# relays_1-4_DS4E.net
KiCad netlist of a schematic drawn in Altium Designer
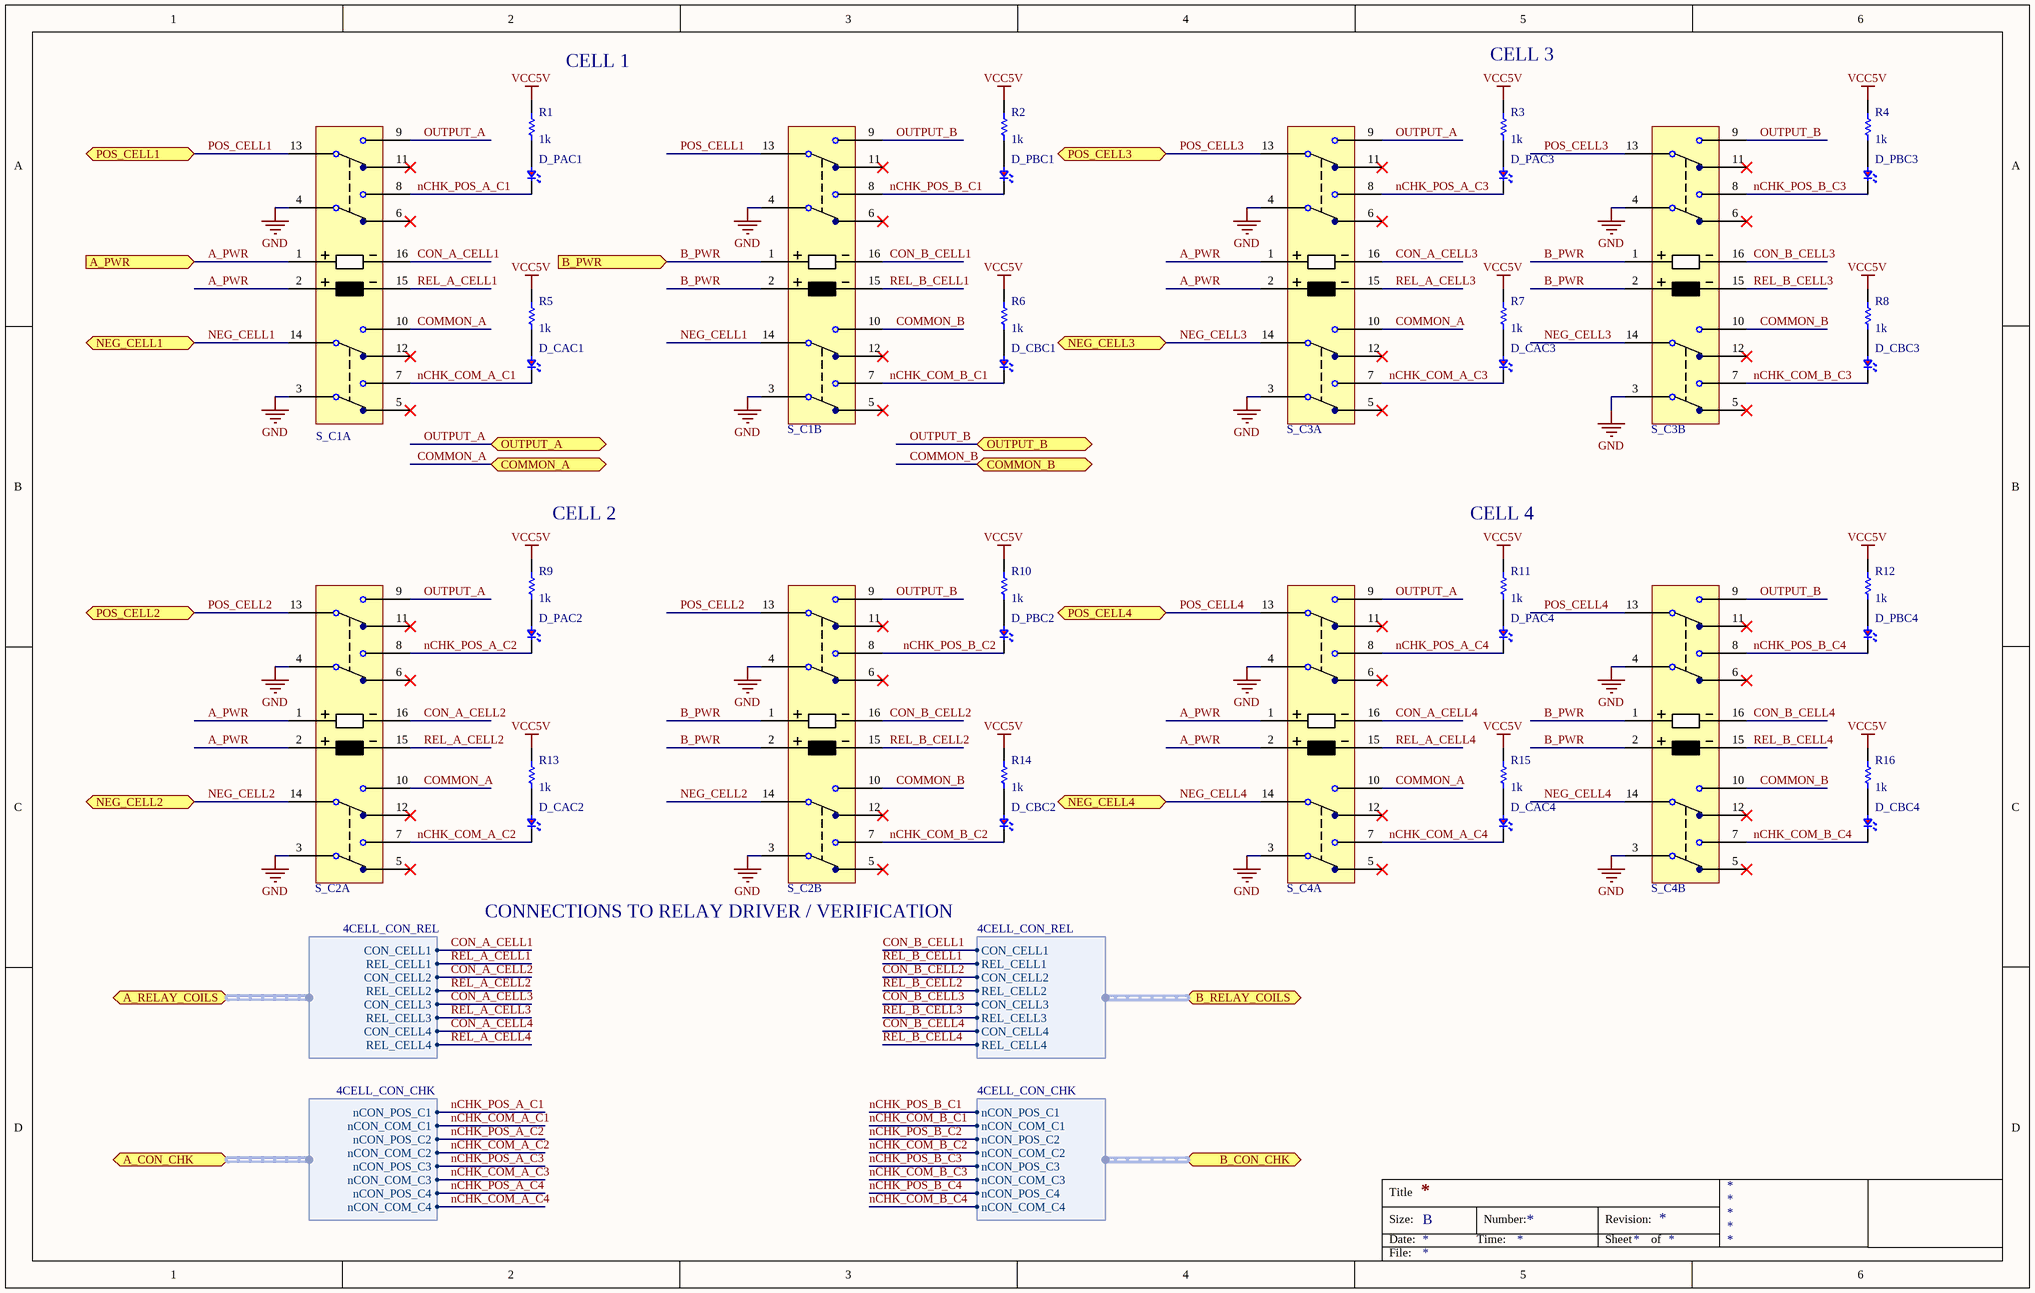
[diagram p0: relays_1-4_DS4E.SchDoc]

(export (version "E")
  (design (tool "Eeschema 10.0.6"))
  (components
    (comp (ref "D_CAC1")
      (value "Red LED")
      (footprint "LEDRD100W25D118H196")
      (description "LED 5MM RED DIFF 6\"LDS PANEL MT")
      (fields
        (field (name "MANUFACTURER") "Lumex Opto/Components Inc.")
        (field (name "MANUFACTURER PART NUMBER") "SSI-LXH600ID-150")
      )
      (libsource (lib "mechanart_oshw") (part "LED-RED"))
    )
    (comp (ref "D_CAC2")
      (value "Red LED")
      (footprint "LEDRD100W25D118H196")
      (description "LED 5MM RED DIFF 6\"LDS PANEL MT")
      (fields
        (field (name "MANUFACTURER") "Lumex Opto/Components Inc.")
        (field (name "MANUFACTURER PART NUMBER") "SSI-LXH600ID-150")
      )
      (libsource (lib "mechanart_oshw") (part "LED-RED"))
    )
    (comp (ref "D_CAC3")
      (value "Red LED")
      (footprint "LEDRD100W25D118H196")
      (description "LED 5MM RED DIFF 6\"LDS PANEL MT")
      (fields
        (field (name "MANUFACTURER") "Lumex Opto/Components Inc.")
        (field (name "MANUFACTURER PART NUMBER") "SSI-LXH600ID-150")
      )
      (libsource (lib "mechanart_oshw") (part "LED-RED"))
    )
    (comp (ref "D_CAC4")
      (value "Red LED")
      (footprint "LEDRD100W25D118H196")
      (description "LED 5MM RED DIFF 6\"LDS PANEL MT")
      (fields
        (field (name "MANUFACTURER") "Lumex Opto/Components Inc.")
        (field (name "MANUFACTURER PART NUMBER") "SSI-LXH600ID-150")
      )
      (libsource (lib "mechanart_oshw") (part "LED-RED"))
    )
    (comp (ref "D_CBC1")
      (value "Red LED")
      (footprint "LEDRD100W25D118H196")
      (description "LED 5MM RED DIFF 6\"LDS PANEL MT")
      (fields
        (field (name "MANUFACTURER") "Lumex Opto/Components Inc.")
        (field (name "MANUFACTURER PART NUMBER") "SSI-LXH600ID-150")
      )
      (libsource (lib "mechanart_oshw") (part "LED-RED"))
    )
    (comp (ref "D_CBC2")
      (value "Red LED")
      (footprint "LEDRD100W25D118H196")
      (description "LED 5MM RED DIFF 6\"LDS PANEL MT")
      (fields
        (field (name "MANUFACTURER") "Lumex Opto/Components Inc.")
        (field (name "MANUFACTURER PART NUMBER") "SSI-LXH600ID-150")
      )
      (libsource (lib "mechanart_oshw") (part "LED-RED"))
    )
    (comp (ref "D_CBC3")
      (value "Red LED")
      (footprint "LEDRD100W25D118H196")
      (description "LED 5MM RED DIFF 6\"LDS PANEL MT")
      (fields
        (field (name "MANUFACTURER") "Lumex Opto/Components Inc.")
        (field (name "MANUFACTURER PART NUMBER") "SSI-LXH600ID-150")
      )
      (libsource (lib "mechanart_oshw") (part "LED-RED"))
    )
    (comp (ref "D_CBC4")
      (value "Red LED")
      (footprint "LEDRD100W25D118H196")
      (description "LED 5MM RED DIFF 6\"LDS PANEL MT")
      (fields
        (field (name "MANUFACTURER") "Lumex Opto/Components Inc.")
        (field (name "MANUFACTURER PART NUMBER") "SSI-LXH600ID-150")
      )
      (libsource (lib "mechanart_oshw") (part "LED-RED"))
    )
    (comp (ref "D_PAC1")
      (value "Red LED")
      (footprint "LEDRD100W25D118H196")
      (description "LED 5MM RED DIFF 6\"LDS PANEL MT")
      (fields
        (field (name "MANUFACTURER") "Lumex Opto/Components Inc.")
        (field (name "MANUFACTURER PART NUMBER") "SSI-LXH600ID-150")
      )
      (libsource (lib "mechanart_oshw") (part "LED-RED"))
    )
    (comp (ref "D_PAC2")
      (value "Red LED")
      (footprint "LEDRD100W25D118H196")
      (description "LED 5MM RED DIFF 6\"LDS PANEL MT")
      (fields
        (field (name "MANUFACTURER") "Lumex Opto/Components Inc.")
        (field (name "MANUFACTURER PART NUMBER") "SSI-LXH600ID-150")
      )
      (libsource (lib "mechanart_oshw") (part "LED-RED"))
    )
    (comp (ref "D_PAC3")
      (value "Red LED")
      (footprint "LEDRD100W25D118H196")
      (description "LED 5MM RED DIFF 6\"LDS PANEL MT")
      (fields
        (field (name "MANUFACTURER") "Lumex Opto/Components Inc.")
        (field (name "MANUFACTURER PART NUMBER") "SSI-LXH600ID-150")
      )
      (libsource (lib "mechanart_oshw") (part "LED-RED"))
    )
    (comp (ref "D_PAC4")
      (value "Red LED")
      (footprint "LEDRD100W25D118H196")
      (description "LED 5MM RED DIFF 6\"LDS PANEL MT")
      (fields
        (field (name "MANUFACTURER") "Lumex Opto/Components Inc.")
        (field (name "MANUFACTURER PART NUMBER") "SSI-LXH600ID-150")
      )
      (libsource (lib "mechanart_oshw") (part "LED-RED"))
    )
    (comp (ref "D_PBC1")
      (value "Red LED")
      (footprint "LEDRD100W25D118H196")
      (description "LED 5MM RED DIFF 6\"LDS PANEL MT")
      (fields
        (field (name "MANUFACTURER") "Lumex Opto/Components Inc.")
        (field (name "MANUFACTURER PART NUMBER") "SSI-LXH600ID-150")
      )
      (libsource (lib "mechanart_oshw") (part "LED-RED"))
    )
    (comp (ref "D_PBC2")
      (value "Red LED")
      (footprint "LEDRD100W25D118H196")
      (description "LED 5MM RED DIFF 6\"LDS PANEL MT")
      (fields
        (field (name "MANUFACTURER") "Lumex Opto/Components Inc.")
        (field (name "MANUFACTURER PART NUMBER") "SSI-LXH600ID-150")
      )
      (libsource (lib "mechanart_oshw") (part "LED-RED"))
    )
    (comp (ref "D_PBC3")
      (value "Red LED")
      (footprint "LEDRD100W25D118H196")
      (description "LED 5MM RED DIFF 6\"LDS PANEL MT")
      (fields
        (field (name "MANUFACTURER") "Lumex Opto/Components Inc.")
        (field (name "MANUFACTURER PART NUMBER") "SSI-LXH600ID-150")
      )
      (libsource (lib "mechanart_oshw") (part "LED-RED"))
    )
    (comp (ref "D_PBC4")
      (value "Red LED")
      (footprint "LEDRD100W25D118H196")
      (description "LED 5MM RED DIFF 6\"LDS PANEL MT")
      (fields
        (field (name "MANUFACTURER") "Lumex Opto/Components Inc.")
        (field (name "MANUFACTURER PART NUMBER") "SSI-LXH600ID-150")
      )
      (libsource (lib "mechanart_oshw") (part "LED-RED"))
    )
    (comp (ref "R1")
      (value "1k")
      (footprint "RESC2012X75L55N")
      (description "RES SMD 1K OHM 5% 1/2W 0805")
      (fields
        (field (name "MANUFACTURER") "Panasonic Electronic Components")
        (field (name "MANUFACTURER PART NUMBER") "ERJ-P06J102V")
      )
      (libsource (lib "mechanart_oshw") (part "ResSMT"))
    )
    (comp (ref "R2")
      (value "1k")
      (footprint "RESC2012X75L55N")
      (description "RES SMD 1K OHM 5% 1/2W 0805")
      (fields
        (field (name "MANUFACTURER") "Panasonic Electronic Components")
        (field (name "MANUFACTURER PART NUMBER") "ERJ-P06J102V")
      )
      (libsource (lib "mechanart_oshw") (part "ResSMT"))
    )
    (comp (ref "R3")
      (value "1k")
      (footprint "RESC2012X75L55N")
      (description "RES SMD 1K OHM 5% 1/2W 0805")
      (fields
        (field (name "MANUFACTURER") "Panasonic Electronic Components")
        (field (name "MANUFACTURER PART NUMBER") "ERJ-P06J102V")
      )
      (libsource (lib "mechanart_oshw") (part "ResSMT"))
    )
    (comp (ref "R4")
      (value "1k")
      (footprint "RESC2012X75L55N")
      (description "RES SMD 1K OHM 5% 1/2W 0805")
      (fields
        (field (name "MANUFACTURER") "Panasonic Electronic Components")
        (field (name "MANUFACTURER PART NUMBER") "ERJ-P06J102V")
      )
      (libsource (lib "mechanart_oshw") (part "ResSMT"))
    )
    (comp (ref "R5")
      (value "1k")
      (footprint "RESC2012X75L55N")
      (description "RES SMD 1K OHM 5% 1/2W 0805")
      (fields
        (field (name "MANUFACTURER") "Panasonic Electronic Components")
        (field (name "MANUFACTURER PART NUMBER") "ERJ-P06J102V")
      )
      (libsource (lib "mechanart_oshw") (part "ResSMT"))
    )
    (comp (ref "R6")
      (value "1k")
      (footprint "RESC2012X75L55N")
      (description "RES SMD 1K OHM 5% 1/2W 0805")
      (fields
        (field (name "MANUFACTURER") "Panasonic Electronic Components")
        (field (name "MANUFACTURER PART NUMBER") "ERJ-P06J102V")
      )
      (libsource (lib "mechanart_oshw") (part "ResSMT"))
    )
    (comp (ref "R7")
      (value "1k")
      (footprint "RESC2012X75L55N")
      (description "RES SMD 1K OHM 5% 1/2W 0805")
      (fields
        (field (name "MANUFACTURER") "Panasonic Electronic Components")
        (field (name "MANUFACTURER PART NUMBER") "ERJ-P06J102V")
      )
      (libsource (lib "mechanart_oshw") (part "ResSMT"))
    )
    (comp (ref "R8")
      (value "1k")
      (footprint "RESC2012X75L55N")
      (description "RES SMD 1K OHM 5% 1/2W 0805")
      (fields
        (field (name "MANUFACTURER") "Panasonic Electronic Components")
        (field (name "MANUFACTURER PART NUMBER") "ERJ-P06J102V")
      )
      (libsource (lib "mechanart_oshw") (part "ResSMT"))
    )
    (comp (ref "R9")
      (value "1k")
      (footprint "RESC2012X75L55N")
      (description "RES SMD 1K OHM 5% 1/2W 0805")
      (fields
        (field (name "MANUFACTURER") "Panasonic Electronic Components")
        (field (name "MANUFACTURER PART NUMBER") "ERJ-P06J102V")
      )
      (libsource (lib "mechanart_oshw") (part "ResSMT"))
    )
    (comp (ref "R10")
      (value "1k")
      (footprint "RESC2012X75L55N")
      (description "RES SMD 1K OHM 5% 1/2W 0805")
      (fields
        (field (name "MANUFACTURER") "Panasonic Electronic Components")
        (field (name "MANUFACTURER PART NUMBER") "ERJ-P06J102V")
      )
      (libsource (lib "mechanart_oshw") (part "ResSMT"))
    )
    (comp (ref "R11")
      (value "1k")
      (footprint "RESC2012X75L55N")
      (description "RES SMD 1K OHM 5% 1/2W 0805")
      (fields
        (field (name "MANUFACTURER") "Panasonic Electronic Components")
        (field (name "MANUFACTURER PART NUMBER") "ERJ-P06J102V")
      )
      (libsource (lib "mechanart_oshw") (part "ResSMT"))
    )
    (comp (ref "R12")
      (value "1k")
      (footprint "RESC2012X75L55N")
      (description "RES SMD 1K OHM 5% 1/2W 0805")
      (fields
        (field (name "MANUFACTURER") "Panasonic Electronic Components")
        (field (name "MANUFACTURER PART NUMBER") "ERJ-P06J102V")
      )
      (libsource (lib "mechanart_oshw") (part "ResSMT"))
    )
    (comp (ref "R13")
      (value "1k")
      (footprint "RESC2012X75L55N")
      (description "RES SMD 1K OHM 5% 1/2W 0805")
      (fields
        (field (name "MANUFACTURER") "Panasonic Electronic Components")
        (field (name "MANUFACTURER PART NUMBER") "ERJ-P06J102V")
      )
      (libsource (lib "mechanart_oshw") (part "ResSMT"))
    )
    (comp (ref "R14")
      (value "1k")
      (footprint "RESC2012X75L55N")
      (description "RES SMD 1K OHM 5% 1/2W 0805")
      (fields
        (field (name "MANUFACTURER") "Panasonic Electronic Components")
        (field (name "MANUFACTURER PART NUMBER") "ERJ-P06J102V")
      )
      (libsource (lib "mechanart_oshw") (part "ResSMT"))
    )
    (comp (ref "R15")
      (value "1k")
      (footprint "RESC2012X75L55N")
      (description "RES SMD 1K OHM 5% 1/2W 0805")
      (fields
        (field (name "MANUFACTURER") "Panasonic Electronic Components")
        (field (name "MANUFACTURER PART NUMBER") "ERJ-P06J102V")
      )
      (libsource (lib "mechanart_oshw") (part "ResSMT"))
    )
    (comp (ref "R16")
      (value "1k")
      (footprint "RESC2012X75L55N")
      (description "RES SMD 1K OHM 5% 1/2W 0805")
      (fields
        (field (name "MANUFACTURER") "Panasonic Electronic Components")
        (field (name "MANUFACTURER PART NUMBER") "ERJ-P06J102V")
      )
      (libsource (lib "mechanart_oshw") (part "ResSMT"))
    )
    (comp (ref "S_C1A")
      (value "4PDT_RELAY_L2")
      (footprint "L2_4PDT_RELAY")
      (description "RELAY GENERAL PURPOSE 4PDT 2A 5V")
      (fields
        (field (name "MANUFACTURER") "Panasonic Electric Works")
        (field (name "MANUFACTURER PART NUMBER") "DS4E-ML2-DC5V")
      )
      (libsource (lib "mechanart_oshw") (part "4PDT_RELAY_L2"))
    )
    (comp (ref "S_C1B")
      (value "4PDT_RELAY_L2")
      (footprint "L2_4PDT_RELAY")
      (description "RELAY GENERAL PURPOSE 4PDT 2A 5V")
      (fields
        (field (name "MANUFACTURER") "Panasonic Electric Works")
        (field (name "MANUFACTURER PART NUMBER") "DS4E-ML2-DC5V")
      )
      (libsource (lib "mechanart_oshw") (part "4PDT_RELAY_L2"))
    )
    (comp (ref "S_C2A")
      (value "4PDT_RELAY_L2")
      (footprint "L2_4PDT_RELAY")
      (description "RELAY GENERAL PURPOSE 4PDT 2A 5V")
      (fields
        (field (name "MANUFACTURER") "Panasonic Electric Works")
        (field (name "MANUFACTURER PART NUMBER") "DS4E-ML2-DC5V")
      )
      (libsource (lib "mechanart_oshw") (part "4PDT_RELAY_L2"))
    )
    (comp (ref "S_C2B")
      (value "4PDT_RELAY_L2")
      (footprint "L2_4PDT_RELAY")
      (description "RELAY GENERAL PURPOSE 4PDT 2A 5V")
      (fields
        (field (name "MANUFACTURER") "Panasonic Electric Works")
        (field (name "MANUFACTURER PART NUMBER") "DS4E-ML2-DC5V")
      )
      (libsource (lib "mechanart_oshw") (part "4PDT_RELAY_L2"))
    )
    (comp (ref "S_C3A")
      (value "4PDT_RELAY_L2")
      (footprint "L2_4PDT_RELAY")
      (description "RELAY GENERAL PURPOSE 4PDT 2A 5V")
      (fields
        (field (name "MANUFACTURER") "Panasonic Electric Works")
        (field (name "MANUFACTURER PART NUMBER") "DS4E-ML2-DC5V")
      )
      (libsource (lib "mechanart_oshw") (part "4PDT_RELAY_L2"))
    )
    (comp (ref "S_C3B")
      (value "4PDT_RELAY_L2")
      (footprint "L2_4PDT_RELAY")
      (description "RELAY GENERAL PURPOSE 4PDT 2A 5V")
      (fields
        (field (name "MANUFACTURER") "Panasonic Electric Works")
        (field (name "MANUFACTURER PART NUMBER") "DS4E-ML2-DC5V")
      )
      (libsource (lib "mechanart_oshw") (part "4PDT_RELAY_L2"))
    )
    (comp (ref "S_C4A")
      (value "4PDT_RELAY_L2")
      (footprint "L2_4PDT_RELAY")
      (description "RELAY GENERAL PURPOSE 4PDT 2A 5V")
      (fields
        (field (name "MANUFACTURER") "Panasonic Electric Works")
        (field (name "MANUFACTURER PART NUMBER") "DS4E-ML2-DC5V")
      )
      (libsource (lib "mechanart_oshw") (part "4PDT_RELAY_L2"))
    )
    (comp (ref "S_C4B")
      (value "4PDT_RELAY_L2")
      (footprint "L2_4PDT_RELAY")
      (description "RELAY GENERAL PURPOSE 4PDT 2A 5V")
      (fields
        (field (name "MANUFACTURER") "Panasonic Electric Works")
        (field (name "MANUFACTURER PART NUMBER") "DS4E-ML2-DC5V")
      )
      (libsource (lib "mechanart_oshw") (part "4PDT_RELAY_L2"))
    )
  )
  (nets
    (net (code "3") (name "/A_PWR") (class "Default")
      (node (ref "S_C1A") (pin "1") (pinfunction "1_1") (pintype "passive"))
      (node (ref "S_C1A") (pin "2") (pinfunction "2_2") (pintype "passive"))
      (node (ref "S_C2A") (pin "1") (pinfunction "1_1") (pintype "passive"))
      (node (ref "S_C2A") (pin "2") (pinfunction "2_2") (pintype "passive"))
      (node (ref "S_C3A") (pin "1") (pinfunction "1_1") (pintype "passive"))
      (node (ref "S_C3A") (pin "2") (pinfunction "2_2") (pintype "passive"))
      (node (ref "S_C4A") (pin "1") (pinfunction "1_1") (pintype "passive"))
      (node (ref "S_C4A") (pin "2") (pinfunction "2_2") (pintype "passive"))
    )
    (net (code "4") (name "/B_PWR") (class "Default")
      (node (ref "S_C1B") (pin "1") (pinfunction "1_1") (pintype "passive"))
      (node (ref "S_C1B") (pin "2") (pinfunction "2_2") (pintype "passive"))
      (node (ref "S_C2B") (pin "1") (pinfunction "1_1") (pintype "passive"))
      (node (ref "S_C2B") (pin "2") (pinfunction "2_2") (pintype "passive"))
      (node (ref "S_C3B") (pin "1") (pinfunction "1_1") (pintype "passive"))
      (node (ref "S_C3B") (pin "2") (pinfunction "2_2") (pintype "passive"))
      (node (ref "S_C4B") (pin "1") (pinfunction "1_1") (pintype "passive"))
      (node (ref "S_C4B") (pin "2") (pinfunction "2_2") (pintype "passive"))
    )
    (net (code "5") (name "/COMMON_A") (class "Default")
      (node (ref "S_C1A") (pin "10") (pinfunction "10_10") (pintype "passive"))
      (node (ref "S_C2A") (pin "10") (pinfunction "10_10") (pintype "passive"))
      (node (ref "S_C3A") (pin "10") (pinfunction "10_10") (pintype "passive"))
      (node (ref "S_C4A") (pin "10") (pinfunction "10_10") (pintype "passive"))
    )
    (net (code "6") (name "/COMMON_B") (class "Default")
      (node (ref "S_C1B") (pin "10") (pinfunction "10_10") (pintype "passive"))
      (node (ref "S_C2B") (pin "10") (pinfunction "10_10") (pintype "passive"))
      (node (ref "S_C3B") (pin "10") (pinfunction "10_10") (pintype "passive"))
      (node (ref "S_C4B") (pin "10") (pinfunction "10_10") (pintype "passive"))
    )
    (net (code "7") (name "/CON_A_CELL1") (class "Default")
      (node (ref "S_C1A") (pin "16") (pinfunction "16_16") (pintype "passive"))
    )
    (net (code "8") (name "/CON_A_CELL2") (class "Default")
      (node (ref "S_C2A") (pin "16") (pinfunction "16_16") (pintype "passive"))
    )
    (net (code "9") (name "/CON_A_CELL3") (class "Default")
      (node (ref "S_C3A") (pin "16") (pinfunction "16_16") (pintype "passive"))
    )
    (net (code "10") (name "/CON_A_CELL4") (class "Default")
      (node (ref "S_C4A") (pin "16") (pinfunction "16_16") (pintype "passive"))
    )
    (net (code "11") (name "/CON_B_CELL1") (class "Default")
      (node (ref "S_C1B") (pin "16") (pinfunction "16_16") (pintype "passive"))
    )
    (net (code "12") (name "/CON_B_CELL2") (class "Default")
      (node (ref "S_C2B") (pin "16") (pinfunction "16_16") (pintype "passive"))
    )
    (net (code "13") (name "/CON_B_CELL3") (class "Default")
      (node (ref "S_C3B") (pin "16") (pinfunction "16_16") (pintype "passive"))
    )
    (net (code "14") (name "/CON_B_CELL4") (class "Default")
      (node (ref "S_C4B") (pin "16") (pinfunction "16_16") (pintype "passive"))
    )
    (net (code "15") (name "/NEG_CELL1") (class "Default")
      (node (ref "S_C1A") (pin "14") (pinfunction "14_14") (pintype "passive"))
      (node (ref "S_C1B") (pin "14") (pinfunction "14_14") (pintype "passive"))
    )
    (net (code "16") (name "/NEG_CELL2") (class "Default")
      (node (ref "S_C2A") (pin "14") (pinfunction "14_14") (pintype "passive"))
      (node (ref "S_C2B") (pin "14") (pinfunction "14_14") (pintype "passive"))
    )
    (net (code "17") (name "/NEG_CELL3") (class "Default")
      (node (ref "S_C3A") (pin "14") (pinfunction "14_14") (pintype "passive"))
      (node (ref "S_C3B") (pin "14") (pinfunction "14_14") (pintype "passive"))
    )
    (net (code "18") (name "/NEG_CELL4") (class "Default")
      (node (ref "S_C4A") (pin "14") (pinfunction "14_14") (pintype "passive"))
      (node (ref "S_C4B") (pin "14") (pinfunction "14_14") (pintype "passive"))
    )
    (net (code "19") (name "/OUTPUT_A") (class "Default")
      (node (ref "S_C1A") (pin "9") (pinfunction "9_9") (pintype "passive"))
      (node (ref "S_C2A") (pin "9") (pinfunction "9_9") (pintype "passive"))
      (node (ref "S_C3A") (pin "9") (pinfunction "9_9") (pintype "passive"))
      (node (ref "S_C4A") (pin "9") (pinfunction "9_9") (pintype "passive"))
    )
    (net (code "20") (name "/OUTPUT_B") (class "Default")
      (node (ref "S_C1B") (pin "9") (pinfunction "9_9") (pintype "passive"))
      (node (ref "S_C2B") (pin "9") (pinfunction "9_9") (pintype "passive"))
      (node (ref "S_C3B") (pin "9") (pinfunction "9_9") (pintype "passive"))
      (node (ref "S_C4B") (pin "9") (pinfunction "9_9") (pintype "passive"))
    )
    (net (code "21") (name "/POS_CELL1") (class "Default")
      (node (ref "S_C1A") (pin "13") (pinfunction "13_13") (pintype "passive"))
      (node (ref "S_C1B") (pin "13") (pinfunction "13_13") (pintype "passive"))
    )
    (net (code "22") (name "/POS_CELL2") (class "Default")
      (node (ref "S_C2A") (pin "13") (pinfunction "13_13") (pintype "passive"))
      (node (ref "S_C2B") (pin "13") (pinfunction "13_13") (pintype "passive"))
    )
    (net (code "23") (name "/POS_CELL3") (class "Default")
      (node (ref "S_C3A") (pin "13") (pinfunction "13_13") (pintype "passive"))
      (node (ref "S_C3B") (pin "13") (pinfunction "13_13") (pintype "passive"))
    )
    (net (code "24") (name "/POS_CELL4") (class "Default")
      (node (ref "S_C4A") (pin "13") (pinfunction "13_13") (pintype "passive"))
      (node (ref "S_C4B") (pin "13") (pinfunction "13_13") (pintype "passive"))
    )
    (net (code "25") (name "/REL_A_CELL1") (class "Default")
      (node (ref "S_C1A") (pin "15") (pinfunction "15_15") (pintype "passive"))
    )
    (net (code "26") (name "/REL_A_CELL2") (class "Default")
      (node (ref "S_C2A") (pin "15") (pinfunction "15_15") (pintype "passive"))
    )
    (net (code "27") (name "/REL_A_CELL3") (class "Default")
      (node (ref "S_C3A") (pin "15") (pinfunction "15_15") (pintype "passive"))
    )
    (net (code "28") (name "/REL_A_CELL4") (class "Default")
      (node (ref "S_C4A") (pin "15") (pinfunction "15_15") (pintype "passive"))
    )
    (net (code "29") (name "/REL_B_CELL1") (class "Default")
      (node (ref "S_C1B") (pin "15") (pinfunction "15_15") (pintype "passive"))
    )
    (net (code "30") (name "/REL_B_CELL2") (class "Default")
      (node (ref "S_C2B") (pin "15") (pinfunction "15_15") (pintype "passive"))
    )
    (net (code "31") (name "/REL_B_CELL3") (class "Default")
      (node (ref "S_C3B") (pin "15") (pinfunction "15_15") (pintype "passive"))
    )
    (net (code "32") (name "/REL_B_CELL4") (class "Default")
      (node (ref "S_C4B") (pin "15") (pinfunction "15_15") (pintype "passive"))
    )
    (net (code "33") (name "/nCHK_COM_A_C1") (class "Default")
      (node (ref "D_CAC1") (pin "C") (pinfunction "C_C") (pintype "passive"))
      (node (ref "S_C1A") (pin "7") (pinfunction "7_7") (pintype "passive"))
    )
    (net (code "34") (name "/nCHK_COM_A_C2") (class "Default")
      (node (ref "D_CAC2") (pin "C") (pinfunction "C_C") (pintype "passive"))
      (node (ref "S_C2A") (pin "7") (pinfunction "7_7") (pintype "passive"))
    )
    (net (code "35") (name "/nCHK_COM_A_C3") (class "Default")
      (node (ref "D_CAC3") (pin "C") (pinfunction "C_C") (pintype "passive"))
      (node (ref "S_C3A") (pin "7") (pinfunction "7_7") (pintype "passive"))
    )
    (net (code "36") (name "/nCHK_COM_A_C4") (class "Default")
      (node (ref "D_CAC4") (pin "C") (pinfunction "C_C") (pintype "passive"))
      (node (ref "S_C4A") (pin "7") (pinfunction "7_7") (pintype "passive"))
    )
    (net (code "37") (name "/nCHK_COM_B_C1") (class "Default")
      (node (ref "D_CBC1") (pin "C") (pinfunction "C_C") (pintype "passive"))
      (node (ref "S_C1B") (pin "7") (pinfunction "7_7") (pintype "passive"))
    )
    (net (code "38") (name "/nCHK_COM_B_C2") (class "Default")
      (node (ref "D_CBC2") (pin "C") (pinfunction "C_C") (pintype "passive"))
      (node (ref "S_C2B") (pin "7") (pinfunction "7_7") (pintype "passive"))
    )
    (net (code "39") (name "/nCHK_COM_B_C3") (class "Default")
      (node (ref "D_CBC3") (pin "C") (pinfunction "C_C") (pintype "passive"))
      (node (ref "S_C3B") (pin "7") (pinfunction "7_7") (pintype "passive"))
    )
    (net (code "40") (name "/nCHK_COM_B_C4") (class "Default")
      (node (ref "D_CBC4") (pin "C") (pinfunction "C_C") (pintype "passive"))
      (node (ref "S_C4B") (pin "7") (pinfunction "7_7") (pintype "passive"))
    )
    (net (code "41") (name "/nCHK_POS_A_C1") (class "Default")
      (node (ref "D_PAC1") (pin "C") (pinfunction "C_C") (pintype "passive"))
      (node (ref "S_C1A") (pin "8") (pinfunction "8_8") (pintype "passive"))
    )
    (net (code "42") (name "/nCHK_POS_A_C2") (class "Default")
      (node (ref "D_PAC2") (pin "C") (pinfunction "C_C") (pintype "passive"))
      (node (ref "S_C2A") (pin "8") (pinfunction "8_8") (pintype "passive"))
    )
    (net (code "43") (name "/nCHK_POS_A_C3") (class "Default")
      (node (ref "D_PAC3") (pin "C") (pinfunction "C_C") (pintype "passive"))
      (node (ref "S_C3A") (pin "8") (pinfunction "8_8") (pintype "passive"))
    )
    (net (code "44") (name "/nCHK_POS_A_C4") (class "Default")
      (node (ref "D_PAC4") (pin "C") (pinfunction "C_C") (pintype "passive"))
      (node (ref "S_C4A") (pin "8") (pinfunction "8_8") (pintype "passive"))
    )
    (net (code "45") (name "/nCHK_POS_B_C1") (class "Default")
      (node (ref "D_PBC1") (pin "C") (pinfunction "C_C") (pintype "passive"))
      (node (ref "S_C1B") (pin "8") (pinfunction "8_8") (pintype "passive"))
    )
    (net (code "46") (name "/nCHK_POS_B_C2") (class "Default")
      (node (ref "D_PBC2") (pin "C") (pinfunction "C_C") (pintype "passive"))
      (node (ref "S_C2B") (pin "8") (pinfunction "8_8") (pintype "passive"))
    )
    (net (code "47") (name "/nCHK_POS_B_C3") (class "Default")
      (node (ref "D_PBC3") (pin "C") (pinfunction "C_C") (pintype "passive"))
      (node (ref "S_C3B") (pin "8") (pinfunction "8_8") (pintype "passive"))
    )
    (net (code "48") (name "/nCHK_POS_B_C4") (class "Default")
      (node (ref "D_PBC4") (pin "C") (pinfunction "C_C") (pintype "passive"))
      (node (ref "S_C4B") (pin "8") (pinfunction "8_8") (pintype "passive"))
    )
    (net (code "51") (name "GND") (class "Default")
      (node (ref "S_C1A") (pin "3") (pinfunction "3_3") (pintype "passive"))
      (node (ref "S_C1A") (pin "4") (pinfunction "4_4") (pintype "passive"))
      (node (ref "S_C1B") (pin "3") (pinfunction "3_3") (pintype "passive"))
      (node (ref "S_C1B") (pin "4") (pinfunction "4_4") (pintype "passive"))
      (node (ref "S_C2A") (pin "3") (pinfunction "3_3") (pintype "passive"))
      (node (ref "S_C2A") (pin "4") (pinfunction "4_4") (pintype "passive"))
      (node (ref "S_C2B") (pin "3") (pinfunction "3_3") (pintype "passive"))
      (node (ref "S_C2B") (pin "4") (pinfunction "4_4") (pintype "passive"))
      (node (ref "S_C3A") (pin "3") (pinfunction "3_3") (pintype "passive"))
      (node (ref "S_C3A") (pin "4") (pinfunction "4_4") (pintype "passive"))
      (node (ref "S_C3B") (pin "3") (pinfunction "3_3") (pintype "passive"))
      (node (ref "S_C3B") (pin "4") (pinfunction "4_4") (pintype "passive"))
      (node (ref "S_C4A") (pin "3") (pinfunction "3_3") (pintype "passive"))
      (node (ref "S_C4A") (pin "4") (pinfunction "4_4") (pintype "passive"))
      (node (ref "S_C4B") (pin "3") (pinfunction "3_3") (pintype "passive"))
      (node (ref "S_C4B") (pin "4") (pinfunction "4_4") (pintype "passive"))
    )
    (net (code "52") (name "Net-(D_CAC1-PadA)") (class "Default")
      (node (ref "D_CAC1") (pin "A") (pinfunction "A_A") (pintype "passive"))
      (node (ref "R5") (pin "1") (pinfunction "1_1") (pintype "passive"))
    )
    (net (code "53") (name "Net-(D_CAC2-PadA)") (class "Default")
      (node (ref "D_CAC2") (pin "A") (pinfunction "A_A") (pintype "passive"))
      (node (ref "R13") (pin "1") (pinfunction "1_1") (pintype "passive"))
    )
    (net (code "54") (name "Net-(D_CAC3-PadA)") (class "Default")
      (node (ref "D_CAC3") (pin "A") (pinfunction "A_A") (pintype "passive"))
      (node (ref "R7") (pin "1") (pinfunction "1_1") (pintype "passive"))
    )
    (net (code "55") (name "Net-(D_CAC4-PadA)") (class "Default")
      (node (ref "D_CAC4") (pin "A") (pinfunction "A_A") (pintype "passive"))
      (node (ref "R15") (pin "1") (pinfunction "1_1") (pintype "passive"))
    )
    (net (code "56") (name "Net-(D_CBC1-PadA)") (class "Default")
      (node (ref "D_CBC1") (pin "A") (pinfunction "A_A") (pintype "passive"))
      (node (ref "R6") (pin "1") (pinfunction "1_1") (pintype "passive"))
    )
    (net (code "57") (name "Net-(D_CBC2-PadA)") (class "Default")
      (node (ref "D_CBC2") (pin "A") (pinfunction "A_A") (pintype "passive"))
      (node (ref "R14") (pin "1") (pinfunction "1_1") (pintype "passive"))
    )
    (net (code "58") (name "Net-(D_CBC3-PadA)") (class "Default")
      (node (ref "D_CBC3") (pin "A") (pinfunction "A_A") (pintype "passive"))
      (node (ref "R8") (pin "1") (pinfunction "1_1") (pintype "passive"))
    )
    (net (code "59") (name "Net-(D_CBC4-PadA)") (class "Default")
      (node (ref "D_CBC4") (pin "A") (pinfunction "A_A") (pintype "passive"))
      (node (ref "R16") (pin "1") (pinfunction "1_1") (pintype "passive"))
    )
    (net (code "60") (name "Net-(D_PAC1-PadA)") (class "Default")
      (node (ref "D_PAC1") (pin "A") (pinfunction "A_A") (pintype "passive"))
      (node (ref "R1") (pin "1") (pinfunction "1_1") (pintype "passive"))
    )
    (net (code "61") (name "Net-(D_PAC2-PadA)") (class "Default")
      (node (ref "D_PAC2") (pin "A") (pinfunction "A_A") (pintype "passive"))
      (node (ref "R9") (pin "1") (pinfunction "1_1") (pintype "passive"))
    )
    (net (code "62") (name "Net-(D_PAC3-PadA)") (class "Default")
      (node (ref "D_PAC3") (pin "A") (pinfunction "A_A") (pintype "passive"))
      (node (ref "R3") (pin "1") (pinfunction "1_1") (pintype "passive"))
    )
    (net (code "63") (name "Net-(D_PAC4-PadA)") (class "Default")
      (node (ref "D_PAC4") (pin "A") (pinfunction "A_A") (pintype "passive"))
      (node (ref "R11") (pin "1") (pinfunction "1_1") (pintype "passive"))
    )
    (net (code "64") (name "Net-(D_PBC1-PadA)") (class "Default")
      (node (ref "D_PBC1") (pin "A") (pinfunction "A_A") (pintype "passive"))
      (node (ref "R2") (pin "1") (pinfunction "1_1") (pintype "passive"))
    )
    (net (code "65") (name "Net-(D_PBC2-PadA)") (class "Default")
      (node (ref "D_PBC2") (pin "A") (pinfunction "A_A") (pintype "passive"))
      (node (ref "R10") (pin "1") (pinfunction "1_1") (pintype "passive"))
    )
    (net (code "66") (name "Net-(D_PBC3-PadA)") (class "Default")
      (node (ref "D_PBC3") (pin "A") (pinfunction "A_A") (pintype "passive"))
      (node (ref "R4") (pin "1") (pinfunction "1_1") (pintype "passive"))
    )
    (net (code "67") (name "Net-(D_PBC4-PadA)") (class "Default")
      (node (ref "D_PBC4") (pin "A") (pinfunction "A_A") (pintype "passive"))
      (node (ref "R12") (pin "1") (pinfunction "1_1") (pintype "passive"))
    )
    (net (code "68") (name "VCC5V") (class "Default")
      (node (ref "R1") (pin "2") (pinfunction "2_2") (pintype "passive"))
      (node (ref "R10") (pin "2") (pinfunction "2_2") (pintype "passive"))
      (node (ref "R11") (pin "2") (pinfunction "2_2") (pintype "passive"))
      (node (ref "R12") (pin "2") (pinfunction "2_2") (pintype "passive"))
      (node (ref "R13") (pin "2") (pinfunction "2_2") (pintype "passive"))
      (node (ref "R14") (pin "2") (pinfunction "2_2") (pintype "passive"))
      (node (ref "R15") (pin "2") (pinfunction "2_2") (pintype "passive"))
      (node (ref "R16") (pin "2") (pinfunction "2_2") (pintype "passive"))
      (node (ref "R2") (pin "2") (pinfunction "2_2") (pintype "passive"))
      (node (ref "R3") (pin "2") (pinfunction "2_2") (pintype "passive"))
      (node (ref "R4") (pin "2") (pinfunction "2_2") (pintype "passive"))
      (node (ref "R5") (pin "2") (pinfunction "2_2") (pintype "passive"))
      (node (ref "R6") (pin "2") (pinfunction "2_2") (pintype "passive"))
      (node (ref "R7") (pin "2") (pinfunction "2_2") (pintype "passive"))
      (node (ref "R8") (pin "2") (pinfunction "2_2") (pintype "passive"))
      (node (ref "R9") (pin "2") (pinfunction "2_2") (pintype "passive"))
    )
    (net (code "69") (name "unconnected-(S_C1A-Pad5)") (class "Default")
      (node (ref "S_C1A") (pin "5") (pinfunction "5_5") (pintype "passive+no_connect"))
    )
    (net (code "70") (name "unconnected-(S_C1A-Pad6)") (class "Default")
      (node (ref "S_C1A") (pin "6") (pinfunction "6_6") (pintype "passive+no_connect"))
    )
    (net (code "71") (name "unconnected-(S_C1A-Pad11)") (class "Default")
      (node (ref "S_C1A") (pin "11") (pinfunction "11_11") (pintype "passive+no_connect"))
    )
    (net (code "72") (name "unconnected-(S_C1A-Pad12)") (class "Default")
      (node (ref "S_C1A") (pin "12") (pinfunction "12_12") (pintype "passive+no_connect"))
    )
    (net (code "73") (name "unconnected-(S_C1B-Pad5)") (class "Default")
      (node (ref "S_C1B") (pin "5") (pinfunction "5_5") (pintype "passive+no_connect"))
    )
    (net (code "74") (name "unconnected-(S_C1B-Pad6)") (class "Default")
      (node (ref "S_C1B") (pin "6") (pinfunction "6_6") (pintype "passive+no_connect"))
    )
    (net (code "75") (name "unconnected-(S_C1B-Pad11)") (class "Default")
      (node (ref "S_C1B") (pin "11") (pinfunction "11_11") (pintype "passive+no_connect"))
    )
    (net (code "76") (name "unconnected-(S_C1B-Pad12)") (class "Default")
      (node (ref "S_C1B") (pin "12") (pinfunction "12_12") (pintype "passive+no_connect"))
    )
    (net (code "77") (name "unconnected-(S_C2A-Pad5)") (class "Default")
      (node (ref "S_C2A") (pin "5") (pinfunction "5_5") (pintype "passive+no_connect"))
    )
    (net (code "78") (name "unconnected-(S_C2A-Pad6)") (class "Default")
      (node (ref "S_C2A") (pin "6") (pinfunction "6_6") (pintype "passive+no_connect"))
    )
    (net (code "79") (name "unconnected-(S_C2A-Pad11)") (class "Default")
      (node (ref "S_C2A") (pin "11") (pinfunction "11_11") (pintype "passive+no_connect"))
    )
    (net (code "80") (name "unconnected-(S_C2A-Pad12)") (class "Default")
      (node (ref "S_C2A") (pin "12") (pinfunction "12_12") (pintype "passive+no_connect"))
    )
    (net (code "81") (name "unconnected-(S_C2B-Pad5)") (class "Default")
      (node (ref "S_C2B") (pin "5") (pinfunction "5_5") (pintype "passive+no_connect"))
    )
    (net (code "82") (name "unconnected-(S_C2B-Pad6)") (class "Default")
      (node (ref "S_C2B") (pin "6") (pinfunction "6_6") (pintype "passive+no_connect"))
    )
    (net (code "83") (name "unconnected-(S_C2B-Pad11)") (class "Default")
      (node (ref "S_C2B") (pin "11") (pinfunction "11_11") (pintype "passive+no_connect"))
    )
    (net (code "84") (name "unconnected-(S_C2B-Pad12)") (class "Default")
      (node (ref "S_C2B") (pin "12") (pinfunction "12_12") (pintype "passive+no_connect"))
    )
    (net (code "85") (name "unconnected-(S_C3A-Pad5)") (class "Default")
      (node (ref "S_C3A") (pin "5") (pinfunction "5_5") (pintype "passive+no_connect"))
    )
    (net (code "86") (name "unconnected-(S_C3A-Pad6)") (class "Default")
      (node (ref "S_C3A") (pin "6") (pinfunction "6_6") (pintype "passive+no_connect"))
    )
    (net (code "87") (name "unconnected-(S_C3A-Pad11)") (class "Default")
      (node (ref "S_C3A") (pin "11") (pinfunction "11_11") (pintype "passive+no_connect"))
    )
    (net (code "88") (name "unconnected-(S_C3A-Pad12)") (class "Default")
      (node (ref "S_C3A") (pin "12") (pinfunction "12_12") (pintype "passive+no_connect"))
    )
    (net (code "89") (name "unconnected-(S_C3B-Pad5)") (class "Default")
      (node (ref "S_C3B") (pin "5") (pinfunction "5_5") (pintype "passive+no_connect"))
    )
    (net (code "90") (name "unconnected-(S_C3B-Pad6)") (class "Default")
      (node (ref "S_C3B") (pin "6") (pinfunction "6_6") (pintype "passive+no_connect"))
    )
    (net (code "91") (name "unconnected-(S_C3B-Pad11)") (class "Default")
      (node (ref "S_C3B") (pin "11") (pinfunction "11_11") (pintype "passive+no_connect"))
    )
    (net (code "92") (name "unconnected-(S_C3B-Pad12)") (class "Default")
      (node (ref "S_C3B") (pin "12") (pinfunction "12_12") (pintype "passive+no_connect"))
    )
    (net (code "93") (name "unconnected-(S_C4A-Pad5)") (class "Default")
      (node (ref "S_C4A") (pin "5") (pinfunction "5_5") (pintype "passive+no_connect"))
    )
    (net (code "94") (name "unconnected-(S_C4A-Pad6)") (class "Default")
      (node (ref "S_C4A") (pin "6") (pinfunction "6_6") (pintype "passive+no_connect"))
    )
    (net (code "95") (name "unconnected-(S_C4A-Pad11)") (class "Default")
      (node (ref "S_C4A") (pin "11") (pinfunction "11_11") (pintype "passive+no_connect"))
    )
    (net (code "96") (name "unconnected-(S_C4A-Pad12)") (class "Default")
      (node (ref "S_C4A") (pin "12") (pinfunction "12_12") (pintype "passive+no_connect"))
    )
    (net (code "97") (name "unconnected-(S_C4B-Pad5)") (class "Default")
      (node (ref "S_C4B") (pin "5") (pinfunction "5_5") (pintype "passive+no_connect"))
    )
    (net (code "98") (name "unconnected-(S_C4B-Pad6)") (class "Default")
      (node (ref "S_C4B") (pin "6") (pinfunction "6_6") (pintype "passive+no_connect"))
    )
    (net (code "99") (name "unconnected-(S_C4B-Pad11)") (class "Default")
      (node (ref "S_C4B") (pin "11") (pinfunction "11_11") (pintype "passive+no_connect"))
    )
    (net (code "100") (name "unconnected-(S_C4B-Pad12)") (class "Default")
      (node (ref "S_C4B") (pin "12") (pinfunction "12_12") (pintype "passive+no_connect"))
    )
  )
)
